# eg4duino_fin.net
KiCad netlist of a schematic drawn in EAGLE
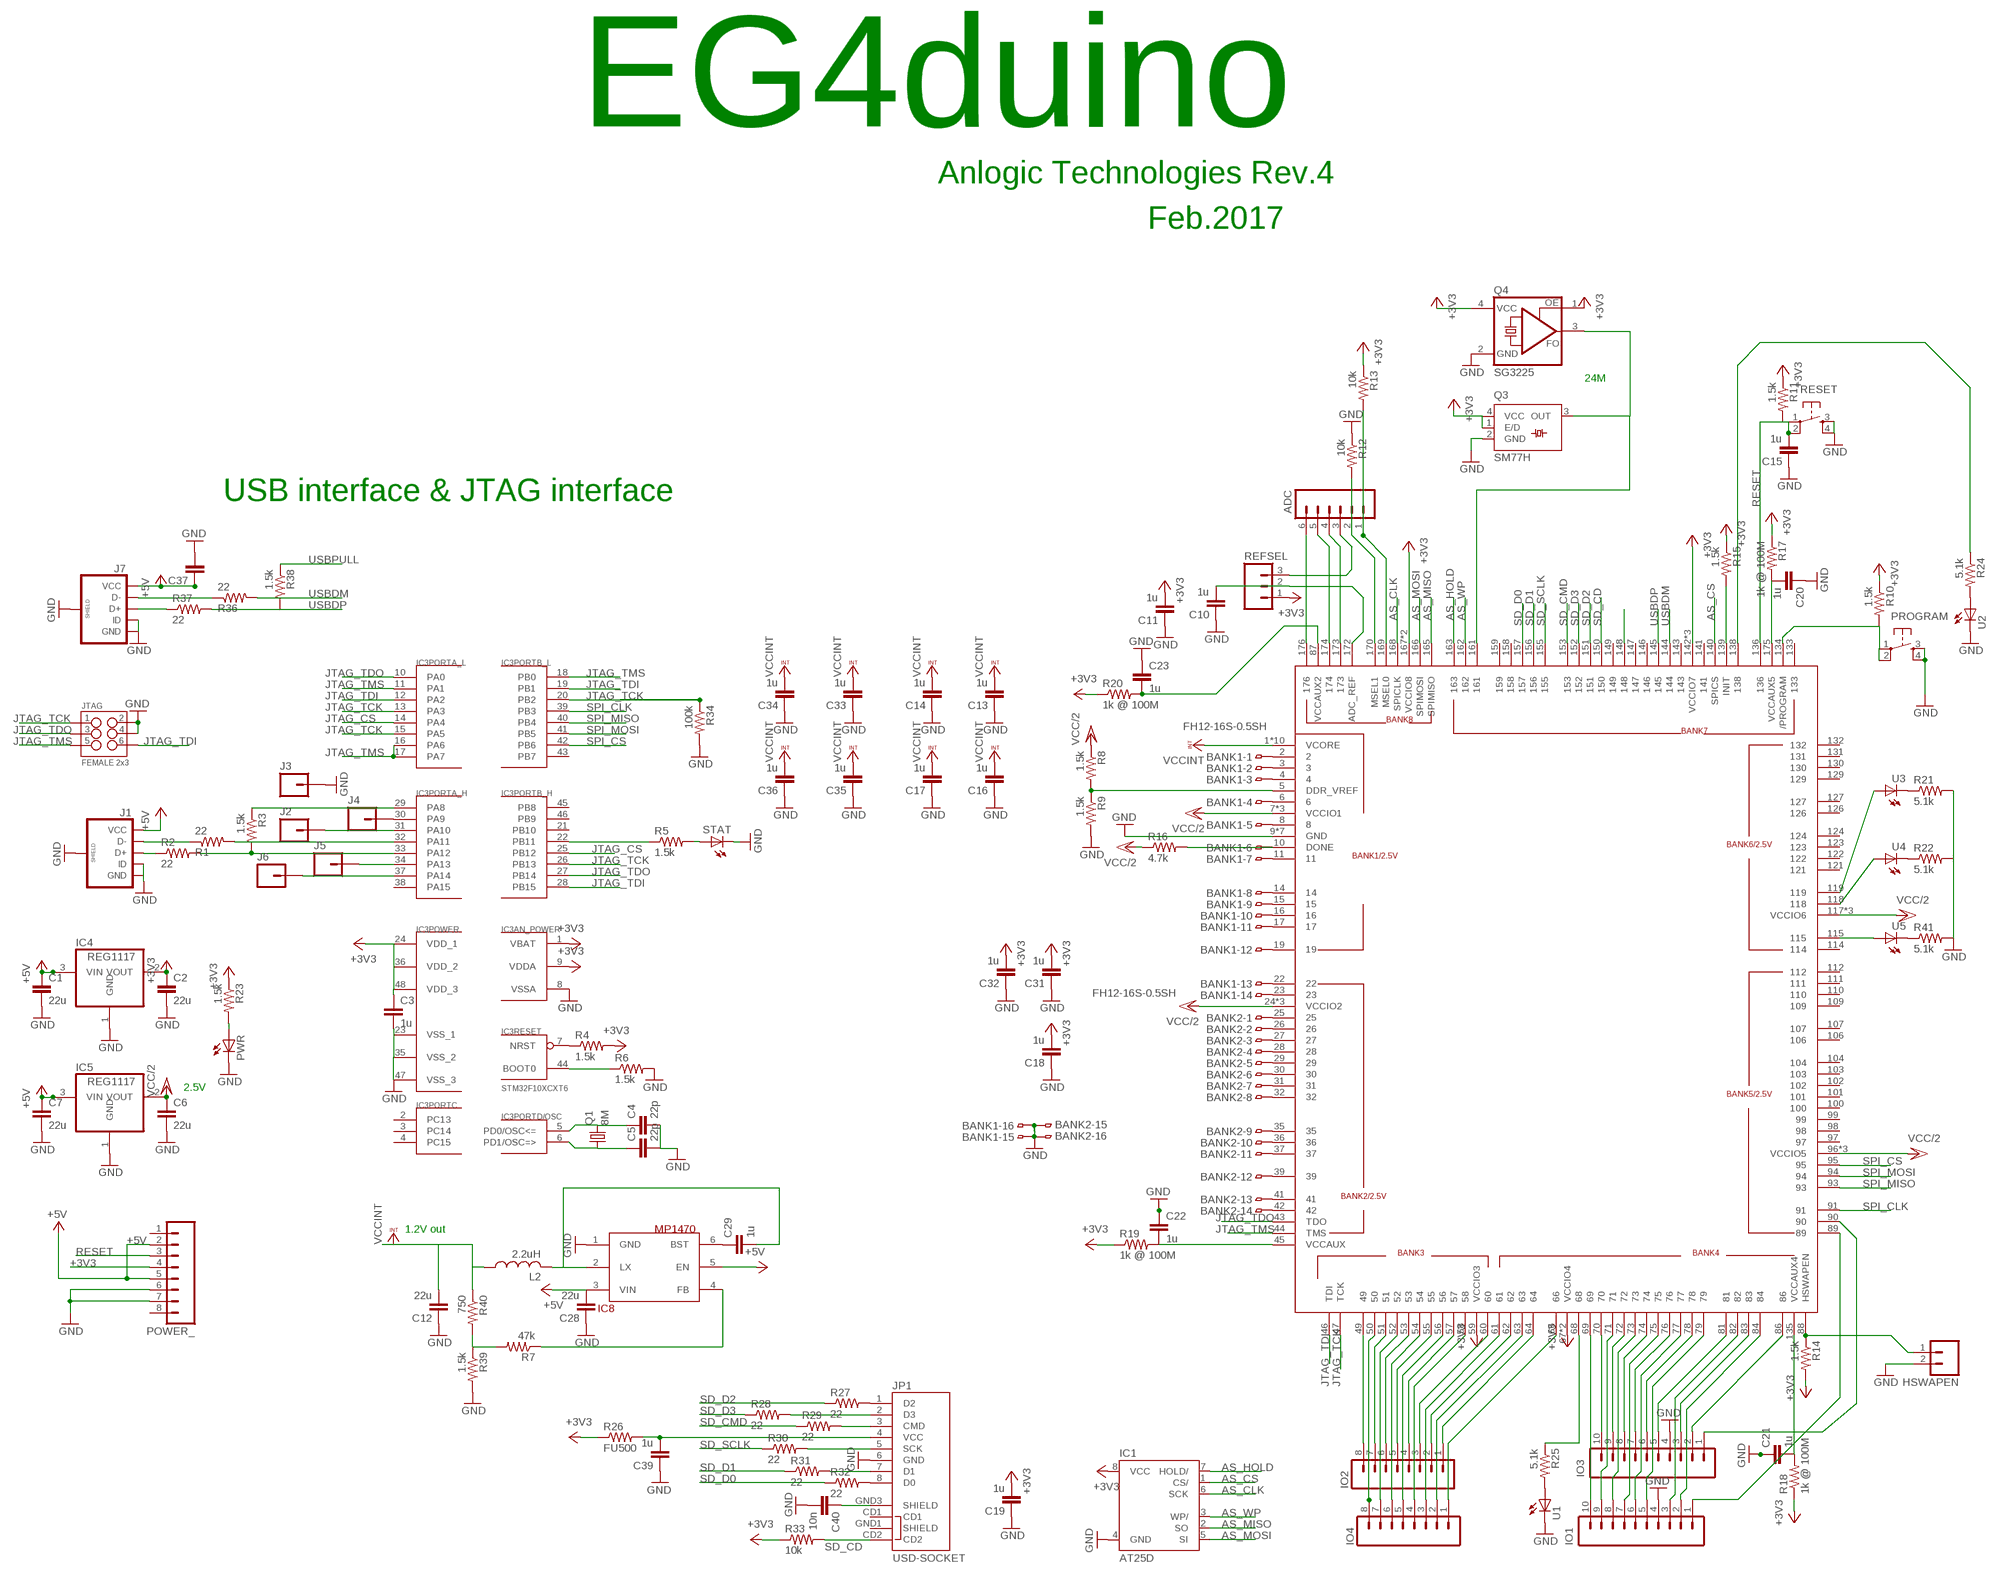
[diagram p0: schematic, sheet 1, part 1 of 2]
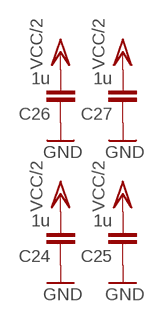
[diagram p1: schematic, sheet 1, part 2 of 2]

(export (version "E")
  (design (tool "Eeschema 10.0.6"))
  (components
    (comp (ref "ADC")
      (value "M06SILK_FEMALE_PTH")
      (footprint "eagle-import:1X06")
      (libsource (lib "eagle-import") (part "M06SILK_FEMALE_PTH"))
    )
    (comp (ref "BANK1")
      (value "FH12-16S-0.5SH")
      (footprint "eagle-import:FH12-16S-0.5SH")
      (fields (field (name "MPN") "FH12-16S-0.5SH(55)"))
      (libsource (lib "eagle-import") (part "FH12-16S-0.5SH"))
    )
    (comp (ref "BANK2")
      (value "FH12-16S-0.5SH")
      (footprint "eagle-import:FH12-16S-0.5SH")
      (fields (field (name "MPN") "FH12-16S-0.5SH(55)"))
      (libsource (lib "eagle-import") (part "FH12-16S-0.5SH"))
    )
    (comp (ref "C1")
      (value "22u")
      (footprint "eagle-import:C0805")
      (libsource (lib "eagle-import") (part "C-EUC0805"))
    )
    (comp (ref "C2")
      (value "22u")
      (footprint "eagle-import:C0805")
      (libsource (lib "eagle-import") (part "C-EUC0805"))
    )
    (comp (ref "C3")
      (value "1u")
      (footprint "eagle-import:C0805")
      (libsource (lib "eagle-import") (part "C-EUC0805"))
    )
    (comp (ref "C4")
      (value "22p")
      (footprint "eagle-import:C0805")
      (libsource (lib "eagle-import") (part "C-EUC0805"))
    )
    (comp (ref "C5")
      (value "22p")
      (footprint "eagle-import:C0805")
      (libsource (lib "eagle-import") (part "C-EUC0805"))
    )
    (comp (ref "C6")
      (value "22u")
      (footprint "eagle-import:C0805")
      (libsource (lib "eagle-import") (part "C-EUC0805"))
    )
    (comp (ref "C7")
      (value "22u")
      (footprint "eagle-import:C0805")
      (libsource (lib "eagle-import") (part "C-EUC0805"))
    )
    (comp (ref "C10")
      (value "1u")
      (footprint "eagle-import:C0805")
      (libsource (lib "eagle-import") (part "C-EUC0805"))
    )
    (comp (ref "C11")
      (value "1u")
      (footprint "eagle-import:C0805")
      (libsource (lib "eagle-import") (part "C-EUC0805"))
    )
    (comp (ref "C12")
      (value "22u")
      (footprint "eagle-import:C0805")
      (libsource (lib "eagle-import") (part "C-EUC0805"))
    )
    (comp (ref "C13")
      (value "1u")
      (footprint "eagle-import:C0805")
      (libsource (lib "eagle-import") (part "C-EUC0805"))
    )
    (comp (ref "C14")
      (value "1u")
      (footprint "eagle-import:C0805")
      (libsource (lib "eagle-import") (part "C-EUC0805"))
    )
    (comp (ref "C15")
      (value "1u")
      (footprint "eagle-import:C0805")
      (libsource (lib "eagle-import") (part "C-EUC0805"))
    )
    (comp (ref "C16")
      (value "1u")
      (footprint "eagle-import:C0805")
      (libsource (lib "eagle-import") (part "C-EUC0805"))
    )
    (comp (ref "C17")
      (value "1u")
      (footprint "eagle-import:C0805")
      (libsource (lib "eagle-import") (part "C-EUC0805"))
    )
    (comp (ref "C18")
      (value "1u")
      (footprint "eagle-import:C0805")
      (libsource (lib "eagle-import") (part "C-EUC0805"))
    )
    (comp (ref "C19")
      (value "1u")
      (footprint "eagle-import:C0805")
      (libsource (lib "eagle-import") (part "C-EUC0805"))
    )
    (comp (ref "C20")
      (value "1u")
      (footprint "eagle-import:C0805")
      (libsource (lib "eagle-import") (part "C-EUC0805"))
    )
    (comp (ref "C21")
      (value "1u")
      (footprint "eagle-import:C0805")
      (libsource (lib "eagle-import") (part "C-EUC0805"))
    )
    (comp (ref "C22")
      (value "1u")
      (footprint "eagle-import:C0805")
      (libsource (lib "eagle-import") (part "C-EUC0805"))
    )
    (comp (ref "C23")
      (value "1u")
      (footprint "eagle-import:C0805")
      (libsource (lib "eagle-import") (part "C-EUC0805"))
    )
    (comp (ref "C24")
      (value "1u")
      (footprint "eagle-import:C0805")
      (libsource (lib "eagle-import") (part "C-EUC0805"))
    )
    (comp (ref "C25")
      (value "1u")
      (footprint "eagle-import:C0805")
      (libsource (lib "eagle-import") (part "C-EUC0805"))
    )
    (comp (ref "C26")
      (value "1u")
      (footprint "eagle-import:C0805")
      (libsource (lib "eagle-import") (part "C-EUC0805"))
    )
    (comp (ref "C27")
      (value "1u")
      (footprint "eagle-import:C0805")
      (libsource (lib "eagle-import") (part "C-EUC0805"))
    )
    (comp (ref "C28")
      (value "22u")
      (footprint "eagle-import:C0805")
      (libsource (lib "eagle-import") (part "C-EUC0805"))
    )
    (comp (ref "C29")
      (value "1u")
      (footprint "eagle-import:C0805")
      (libsource (lib "eagle-import") (part "C-EUC0805"))
    )
    (comp (ref "C31")
      (value "1u")
      (footprint "eagle-import:C0805")
      (libsource (lib "eagle-import") (part "C-EUC0805"))
    )
    (comp (ref "C32")
      (value "1u")
      (footprint "eagle-import:C0805")
      (libsource (lib "eagle-import") (part "C-EUC0805"))
    )
    (comp (ref "C33")
      (value "1u")
      (footprint "eagle-import:C0805")
      (libsource (lib "eagle-import") (part "C-EUC0805"))
    )
    (comp (ref "C34")
      (value "1u")
      (footprint "eagle-import:C0805")
      (libsource (lib "eagle-import") (part "C-EUC0805"))
    )
    (comp (ref "C35")
      (value "1u")
      (footprint "eagle-import:C0805")
      (libsource (lib "eagle-import") (part "C-EUC0805"))
    )
    (comp (ref "C36")
      (value "1u")
      (footprint "eagle-import:C0805")
      (libsource (lib "eagle-import") (part "C-EUC0805"))
    )
    (comp (ref "C37")
      (value "C-EUC0805")
      (footprint "eagle-import:C0805")
      (libsource (lib "eagle-import") (part "C-EUC0805"))
    )
    (comp (ref "C39")
      (value "1u")
      (footprint "eagle-import:C0805")
      (libsource (lib "eagle-import") (part "C-EUC0805"))
    )
    (comp (ref "C40")
      (value "10n")
      (footprint "eagle-import:C0805")
      (libsource (lib "eagle-import") (part "C-EUC0805"))
    )
    (comp (ref "HSWAPEN")
      (value "M02PTH")
      (footprint "eagle-import:1X02")
      (libsource (lib "eagle-import") (part "M02PTH"))
    )
    (comp (ref "IC1")
      (value "AT25D")
      (footprint "eagle-import:SOIC8")
      (libsource (lib "eagle-import") (part "AT25D"))
    )
    (comp (ref "IC2")
      (value "EG4D20EG176")
      (footprint "eagle-import:ELQFP176L")
      (libsource (lib "eagle-import") (part "EG4D20EG176"))
    )
    (comp (ref "IC3")
      (value "STM32F10XCXT6")
      (footprint "eagle-import:TQFP48")
      (libsource (lib "eagle-import") (part "STM32F10XCXT6"))
    )
    (comp (ref "IC4")
      (value "REG1117")
      (footprint "eagle-import:SOT223")
      (libsource (lib "eagle-import") (part "REG1117"))
    )
    (comp (ref "IC5")
      (value "REG1117")
      (footprint "eagle-import:SOT223")
      (libsource (lib "eagle-import") (part "REG1117"))
    )
    (comp (ref "IC8")
      (value "MP1470")
      (footprint "eagle-import:SOT23-6L")
      (libsource (lib "eagle-import") (part "MP1470"))
    )
    (comp (ref "IO1")
      (value "M10SILK_FEMALE_PTH")
      (footprint "eagle-import:1X10")
      (libsource (lib "eagle-import") (part "M10SILK_FEMALE_PTH"))
    )
    (comp (ref "IO2")
      (value "M08SILK_FEMALE_PTH")
      (footprint "eagle-import:1X08")
      (libsource (lib "eagle-import") (part "M08SILK_FEMALE_PTH"))
    )
    (comp (ref "IO3")
      (value "M10SILK_FEMALE_PTH")
      (footprint "eagle-import:1X10")
      (libsource (lib "eagle-import") (part "M10SILK_FEMALE_PTH"))
    )
    (comp (ref "IO4")
      (value "M08SILK_FEMALE_PTH")
      (footprint "eagle-import:1X08")
      (libsource (lib "eagle-import") (part "M08SILK_FEMALE_PTH"))
    )
    (comp (ref "J1")
      (value "USB_MICROB_PLUGCONN-11752")
      (footprint "eagle-import:USB-B-MICRO-SMD_V03")
      (libsource (lib "eagle-import") (part "USB_MICROB_PLUGCONN-11752"))
    )
    (comp (ref "J2")
      (value "M01")
      (footprint "eagle-import:0805SMD")
      (libsource (lib "eagle-import") (part "M01"))
    )
    (comp (ref "J3")
      (value "M01")
      (footprint "eagle-import:0805SMD")
      (libsource (lib "eagle-import") (part "M01"))
    )
    (comp (ref "J4")
      (value "M01")
      (footprint "eagle-import:0805SMD")
      (libsource (lib "eagle-import") (part "M01"))
    )
    (comp (ref "J5")
      (value "M01")
      (footprint "eagle-import:0805SMD")
      (libsource (lib "eagle-import") (part "M01"))
    )
    (comp (ref "J6")
      (value "M01")
      (footprint "eagle-import:0805SMD")
      (libsource (lib "eagle-import") (part "M01"))
    )
    (comp (ref "J7")
      (value "USB_MICROB_PLUGCONN-11752")
      (footprint "eagle-import:USB-B-MICRO-SMD_V03")
      (libsource (lib "eagle-import") (part "USB_MICROB_PLUGCONN-11752"))
    )
    (comp (ref "JP1")
      (value "USD-SOCKET")
      (footprint "eagle-import:MICROSD_1_1")
      (libsource (lib "eagle-import") (part "USD-SOCKET"))
    )
    (comp (ref "JTAG")
      (value "FEMALE 2x3")
      (footprint "eagle-import:2X3")
      (libsource (lib "eagle-import") (part "M03X2FEMALE"))
    )
    (comp (ref "L2")
      (value "2.2uH")
      (footprint "eagle-import:L4532P")
      (libsource (lib "eagle-import") (part "L-USL4532P"))
    )
    (comp (ref "POWER_")
      (value "M08SILK_FEMALE_PTH")
      (footprint "eagle-import:1X08")
      (libsource (lib "eagle-import") (part "M08SILK_FEMALE_PTH"))
    )
    (comp (ref "PROGRAM")
      (value "10-XXSMD")
      (footprint "eagle-import:B3F-10SMD")
      (libsource (lib "eagle-import") (part "10-XXSMD"))
    )
    (comp (ref "PWR")
      (value "LEDCHIP-LED0805")
      (footprint "eagle-import:CHIP-LED0805")
      (libsource (lib "eagle-import") (part "LEDCHIP-LED0805"))
    )
    (comp (ref "Q1")
      (value "8M")
      (footprint "eagle-import:HC49_S")
      (libsource (lib "eagle-import") (part "CRYSTALHC49S"))
    )
    (comp (ref "Q3")
      (value "SM77H")
      (footprint "eagle-import:SM77H")
      (libsource (lib "eagle-import") (part "SM77H"))
    )
    (comp (ref "Q4")
      (value "SG3225")
      (footprint "eagle-import:3225")
      (libsource (lib "eagle-import") (part "SG3225"))
    )
    (comp (ref "R1")
      (value "22")
      (footprint "eagle-import:M0805")
      (libsource (lib "eagle-import") (part "R-US_M0805"))
    )
    (comp (ref "R2")
      (value "22")
      (footprint "eagle-import:M0805")
      (libsource (lib "eagle-import") (part "R-US_M0805"))
    )
    (comp (ref "R3")
      (value "1.5k")
      (footprint "eagle-import:M0805")
      (libsource (lib "eagle-import") (part "R-US_M0805"))
    )
    (comp (ref "R4")
      (value "1.5k")
      (footprint "eagle-import:M0805")
      (libsource (lib "eagle-import") (part "R-US_M0805"))
    )
    (comp (ref "R5")
      (value "1.5k")
      (footprint "eagle-import:M0805")
      (libsource (lib "eagle-import") (part "R-US_M0805"))
    )
    (comp (ref "R6")
      (value "1.5k")
      (footprint "eagle-import:M0805")
      (libsource (lib "eagle-import") (part "R-US_M0805"))
    )
    (comp (ref "R7")
      (value "47k")
      (footprint "eagle-import:R0805")
      (libsource (lib "eagle-import") (part "R-US_R0805"))
    )
    (comp (ref "R8")
      (value "1.5k")
      (footprint "eagle-import:R0805")
      (libsource (lib "eagle-import") (part "R-US_R0805"))
    )
    (comp (ref "R9")
      (value "1.5k")
      (footprint "eagle-import:R0805")
      (libsource (lib "eagle-import") (part "R-US_R0805"))
    )
    (comp (ref "R10")
      (value "1.5k")
      (footprint "eagle-import:R0603")
      (libsource (lib "eagle-import") (part "R-US_R0603"))
    )
    (comp (ref "R11")
      (value "1.5k")
      (footprint "eagle-import:R0805")
      (libsource (lib "eagle-import") (part "R-US_R0805"))
    )
    (comp (ref "R12")
      (value "10k")
      (footprint "eagle-import:R0805")
      (libsource (lib "eagle-import") (part "R-US_R0805"))
    )
    (comp (ref "R13")
      (value "10k")
      (footprint "eagle-import:R0805")
      (libsource (lib "eagle-import") (part "R-US_R0805"))
    )
    (comp (ref "R14")
      (value "1.5k")
      (footprint "eagle-import:R0805")
      (libsource (lib "eagle-import") (part "R-US_R0805"))
    )
    (comp (ref "R15")
      (value "1.5k")
      (footprint "eagle-import:R0805")
      (libsource (lib "eagle-import") (part "R-US_R0805"))
    )
    (comp (ref "R16")
      (value "4.7k")
      (footprint "eagle-import:R0603")
      (libsource (lib "eagle-import") (part "R-US_R0603"))
    )
    (comp (ref "R17")
      (value "1k @ 100M")
      (footprint "eagle-import:R0805")
      (libsource (lib "eagle-import") (part "R-US_R0805"))
    )
    (comp (ref "R18")
      (value "1k @ 100M")
      (footprint "eagle-import:R0805")
      (libsource (lib "eagle-import") (part "R-US_R0805"))
    )
    (comp (ref "R19")
      (value "1k @ 100M")
      (footprint "eagle-import:R0805")
      (libsource (lib "eagle-import") (part "R-US_R0805"))
    )
    (comp (ref "R20")
      (value "1k @ 100M")
      (footprint "eagle-import:R0805")
      (libsource (lib "eagle-import") (part "R-US_R0805"))
    )
    (comp (ref "R21")
      (value "5.1k")
      (footprint "eagle-import:M0805")
      (libsource (lib "eagle-import") (part "R-US_M0805"))
    )
    (comp (ref "R22")
      (value "5.1k")
      (footprint "eagle-import:M0805")
      (libsource (lib "eagle-import") (part "R-US_M0805"))
    )
    (comp (ref "R23")
      (value "1.5k")
      (footprint "eagle-import:M0805")
      (libsource (lib "eagle-import") (part "R-US_M0805"))
    )
    (comp (ref "R24")
      (value "5.1k")
      (footprint "eagle-import:M0805")
      (libsource (lib "eagle-import") (part "R-US_M0805"))
    )
    (comp (ref "R25")
      (value "5.1k")
      (footprint "eagle-import:M0805")
      (libsource (lib "eagle-import") (part "R-US_M0805"))
    )
    (comp (ref "R26")
      (value "FU500")
      (footprint "eagle-import:R0805")
      (libsource (lib "eagle-import") (part "R-US_R0805"))
    )
    (comp (ref "R27")
      (value "22")
      (footprint "eagle-import:R0201")
      (libsource (lib "eagle-import") (part "R-US_R0201"))
    )
    (comp (ref "R28")
      (value "22")
      (footprint "eagle-import:R0201")
      (libsource (lib "eagle-import") (part "R-US_R0201"))
    )
    (comp (ref "R29")
      (value "22")
      (footprint "eagle-import:R0201")
      (libsource (lib "eagle-import") (part "R-US_R0201"))
    )
    (comp (ref "R30")
      (value "22")
      (footprint "eagle-import:R0201")
      (libsource (lib "eagle-import") (part "R-US_R0201"))
    )
    (comp (ref "R31")
      (value "22")
      (footprint "eagle-import:R0201")
      (libsource (lib "eagle-import") (part "R-US_R0201"))
    )
    (comp (ref "R32")
      (value "22")
      (footprint "eagle-import:R0201")
      (libsource (lib "eagle-import") (part "R-US_R0201"))
    )
    (comp (ref "R33")
      (value "10k")
      (footprint "eagle-import:R0805")
      (libsource (lib "eagle-import") (part "R-US_R0805"))
    )
    (comp (ref "R34")
      (value "100k")
      (footprint "eagle-import:R0603")
      (libsource (lib "eagle-import") (part "R-US_R0603"))
    )
    (comp (ref "R36")
      (value "22")
      (footprint "eagle-import:R0603W")
      (libsource (lib "eagle-import") (part "R-US_R0603W"))
    )
    (comp (ref "R37")
      (value "22")
      (footprint "eagle-import:R0603W")
      (libsource (lib "eagle-import") (part "R-US_R0603W"))
    )
    (comp (ref "R38")
      (value "1.5k")
      (footprint "eagle-import:R0603")
      (libsource (lib "eagle-import") (part "R-US_R0603"))
    )
    (comp (ref "R39")
      (value "1.5k")
      (footprint "eagle-import:R0805")
      (libsource (lib "eagle-import") (part "R-US_R0805"))
    )
    (comp (ref "R40")
      (value "750")
      (footprint "eagle-import:R0805")
      (libsource (lib "eagle-import") (part "R-US_R0805"))
    )
    (comp (ref "R41")
      (value "5.1k")
      (footprint "eagle-import:M0805")
      (libsource (lib "eagle-import") (part "R-US_M0805"))
    )
    (comp (ref "REFSEL")
      (value "M03PTH")
      (footprint "eagle-import:1X03")
      (libsource (lib "eagle-import") (part "M03PTH"))
    )
    (comp (ref "RESET")
      (value "10-XXSMD")
      (footprint "eagle-import:B3F-10SMD")
      (libsource (lib "eagle-import") (part "10-XXSMD"))
    )
    (comp (ref "STAT")
      (value "LEDCHIP-LED0805")
      (footprint "eagle-import:CHIP-LED0805")
      (libsource (lib "eagle-import") (part "LEDCHIP-LED0805"))
    )
    (comp (ref "U1")
      (value "LEDCHIP-LED0805")
      (footprint "eagle-import:CHIP-LED0805")
      (libsource (lib "eagle-import") (part "LEDCHIP-LED0805"))
    )
    (comp (ref "U2")
      (value "LEDCHIP-LED0805")
      (footprint "eagle-import:CHIP-LED0805")
      (libsource (lib "eagle-import") (part "LEDCHIP-LED0805"))
    )
    (comp (ref "U3")
      (value "LEDCHIP-LED0805")
      (footprint "eagle-import:CHIP-LED0805")
      (libsource (lib "eagle-import") (part "LEDCHIP-LED0805"))
    )
    (comp (ref "U4")
      (value "LEDCHIP-LED0805")
      (footprint "eagle-import:CHIP-LED0805")
      (libsource (lib "eagle-import") (part "LEDCHIP-LED0805"))
    )
    (comp (ref "U5")
      (value "LEDCHIP-LED0805")
      (footprint "eagle-import:CHIP-LED0805")
      (libsource (lib "eagle-import") (part "LEDCHIP-LED0805"))
    )
  )
  (nets
    (net (code "1") (name "+3V3") (class "Default")
      (node (ref "C11") (pin "2") (pinfunction "2_2") (pintype "passive"))
      (node (ref "C18") (pin "2") (pinfunction "2_2") (pintype "passive"))
      (node (ref "C19") (pin "2") (pinfunction "2_2") (pintype "passive"))
      (node (ref "C2") (pin "1") (pinfunction "1_1") (pintype "passive"))
      (node (ref "C3") (pin "1") (pinfunction "1_1") (pintype "passive"))
      (node (ref "C31") (pin "2") (pinfunction "2_2") (pintype "passive"))
      (node (ref "C32") (pin "2") (pinfunction "2_2") (pintype "passive"))
      (node (ref "IC1") (pin "8") (pinfunction "VCC_8") (pintype "power_in"))
      (node (ref "IC2") (pin "142") (pinfunction "VCCIO7_142") (pintype "bidirectional"))
      (node (ref "IC2") (pin "154") (pinfunction "VCCIO7_154") (pintype "bidirectional"))
      (node (ref "IC2") (pin "160") (pinfunction "VCCIO7_160") (pintype "bidirectional"))
      (node (ref "IC2") (pin "167") (pinfunction "VCCIO8_167") (pintype "bidirectional"))
      (node (ref "IC2") (pin "171") (pinfunction "VCCIO8_171") (pintype "bidirectional"))
      (node (ref "IC2") (pin "59") (pinfunction "VCCIO3_59") (pintype "bidirectional"))
      (node (ref "IC2") (pin "67") (pinfunction "VCCIO4_67") (pintype "bidirectional"))
      (node (ref "IC2") (pin "80") (pinfunction "VCCIO4_80") (pintype "bidirectional"))
      (node (ref "IC3") (pin "1") (pinfunction "VBAT_1") (pintype "power_in"))
      (node (ref "IC3") (pin "24") (pinfunction "VDD_1_24") (pintype "power_in"))
      (node (ref "IC3") (pin "36") (pinfunction "VDD_2_36") (pintype "power_in"))
      (node (ref "IC3") (pin "48") (pinfunction "VDD_3_48") (pintype "power_in"))
      (node (ref "IC3") (pin "9") (pinfunction "VDDA_9") (pintype "power_in"))
      (node (ref "IC4") (pin "2") (pinfunction "VOUT_2") (pintype "output"))
      (node (ref "POWER_") (pin "4") (pinfunction "4_4") (pintype "passive"))
      (node (ref "Q3") (pin "1") (pinfunction "E/D_1") (pintype "input"))
      (node (ref "Q3") (pin "4") (pinfunction "VCC_4") (pintype "power_in"))
      (node (ref "Q4") (pin "1") (pinfunction "OE_1") (pintype "input"))
      (node (ref "Q4") (pin "4") (pinfunction "VCC_4") (pintype "power_in"))
      (node (ref "R10") (pin "1") (pinfunction "1_1") (pintype "passive"))
      (node (ref "R11") (pin "1") (pinfunction "1_1") (pintype "passive"))
      (node (ref "R13") (pin "1") (pinfunction "1_1") (pintype "passive"))
      (node (ref "R14") (pin "2") (pinfunction "2_2") (pintype "passive"))
      (node (ref "R15") (pin "1") (pinfunction "1_1") (pintype "passive"))
      (node (ref "R17") (pin "1") (pinfunction "1_1") (pintype "passive"))
      (node (ref "R18") (pin "1") (pinfunction "1_1") (pintype "passive"))
      (node (ref "R19") (pin "1") (pinfunction "1_1") (pintype "passive"))
      (node (ref "R20") (pin "1") (pinfunction "1_1") (pintype "passive"))
      (node (ref "R23") (pin "1") (pinfunction "1_1") (pintype "passive"))
      (node (ref "R26") (pin "1") (pinfunction "1_1") (pintype "passive"))
      (node (ref "R33") (pin "1") (pinfunction "1_1") (pintype "passive"))
      (node (ref "R4") (pin "2") (pinfunction "2_2") (pintype "passive"))
      (node (ref "REFSEL") (pin "1") (pinfunction "1_1") (pintype "passive"))
    )
    (net (code "2") (name "+5V") (class "Default")
      (node (ref "C1") (pin "1") (pinfunction "1_1") (pintype "passive"))
      (node (ref "C28") (pin "2") (pinfunction "2_2") (pintype "passive"))
      (node (ref "C37") (pin "1") (pinfunction "1_1") (pintype "passive"))
      (node (ref "C7") (pin "1") (pinfunction "1_1") (pintype "passive"))
      (node (ref "IC4") (pin "3") (pinfunction "VIN_3") (pintype "input"))
      (node (ref "IC5") (pin "3") (pinfunction "VIN_3") (pintype "input"))
      (node (ref "IC8") (pin "3") (pinfunction "VIN_3") (pintype "power_in"))
      (node (ref "IC8") (pin "5") (pinfunction "EN_5") (pintype "bidirectional"))
      (node (ref "J1") (pin "VBUS") (pinfunction "VCC_VBUS") (pintype "bidirectional"))
      (node (ref "J7") (pin "VBUS") (pinfunction "VCC_VBUS") (pintype "bidirectional"))
      (node (ref "POWER_") (pin "2") (pinfunction "2_2") (pintype "passive"))
      (node (ref "POWER_") (pin "5") (pinfunction "5_5") (pintype "passive"))
    )
    (net (code "3") (name "/AS_CLK") (class "Default")
      (node (ref "IC1") (pin "6") (pinfunction "SCK_6") (pintype "bidirectional"))
      (node (ref "IC2") (pin "168") (pinfunction "SPICLK_168") (pintype "bidirectional"))
    )
    (net (code "4") (name "/AS_CS") (class "Default")
      (node (ref "IC1") (pin "1") (pinfunction "CS/_1") (pintype "input"))
      (node (ref "IC2") (pin "140") (pinfunction "SPICS_140") (pintype "bidirectional"))
    )
    (net (code "5") (name "/AS_HOLD") (class "Default")
      (node (ref "IC1") (pin "7") (pinfunction "HOLD/_7") (pintype "input"))
      (node (ref "IC2") (pin "163") (pinfunction "163_163") (pintype "bidirectional"))
    )
    (net (code "6") (name "/AS_MISO") (class "Default")
      (node (ref "IC1") (pin "2") (pinfunction "SO_2") (pintype "input"))
      (node (ref "IC2") (pin "165") (pinfunction "SPIMISO_165") (pintype "bidirectional"))
    )
    (net (code "7") (name "/AS_MOSI") (class "Default")
      (node (ref "IC1") (pin "5") (pinfunction "SI_5") (pintype "bidirectional"))
      (node (ref "IC2") (pin "166") (pinfunction "SPIMOSI_166") (pintype "bidirectional"))
    )
    (net (code "8") (name "/AS_WP") (class "Default")
      (node (ref "IC1") (pin "3") (pinfunction "WP/_3") (pintype "input"))
      (node (ref "IC2") (pin "162") (pinfunction "162_162") (pintype "bidirectional"))
    )
    (net (code "9") (name "/JTAG_CS") (class "Default")
      (node (ref "IC3") (pin "14") (pinfunction "PA4_14") (pintype "bidirectional"))
      (node (ref "IC3") (pin "25") (pinfunction "PB12_25") (pintype "bidirectional"))
    )
    (net (code "10") (name "/JTAG_TCK") (class "Default")
      (node (ref "IC2") (pin "47") (pinfunction "TCK_47") (pintype "bidirectional"))
      (node (ref "IC3") (pin "13") (pinfunction "PA3_13") (pintype "bidirectional"))
      (node (ref "IC3") (pin "15") (pinfunction "PA5_15") (pintype "bidirectional"))
      (node (ref "IC3") (pin "20") (pinfunction "PB2_20") (pintype "bidirectional"))
      (node (ref "IC3") (pin "26") (pinfunction "PB13_26") (pintype "bidirectional"))
      (node (ref "JTAG") (pin "1") (pinfunction "1_1") (pintype "bidirectional"))
      (node (ref "R34") (pin "1") (pinfunction "1_1") (pintype "passive"))
    )
    (net (code "11") (name "/JTAG_TDI") (class "Default")
      (node (ref "IC2") (pin "46") (pinfunction "TDI_46") (pintype "bidirectional"))
      (node (ref "IC3") (pin "12") (pinfunction "PA2_12") (pintype "bidirectional"))
      (node (ref "IC3") (pin "19") (pinfunction "PB1_19") (pintype "bidirectional"))
      (node (ref "IC3") (pin "28") (pinfunction "PB15_28") (pintype "bidirectional"))
      (node (ref "JTAG") (pin "6") (pinfunction "6_6") (pintype "bidirectional"))
    )
    (net (code "12") (name "/JTAG_TDO") (class "Default")
      (node (ref "IC2") (pin "43") (pinfunction "TDO_43") (pintype "bidirectional"))
      (node (ref "IC3") (pin "10") (pinfunction "PA0_10") (pintype "bidirectional"))
      (node (ref "IC3") (pin "27") (pinfunction "PB14_27") (pintype "bidirectional"))
      (node (ref "JTAG") (pin "3") (pinfunction "3_3") (pintype "bidirectional"))
    )
    (net (code "13") (name "/JTAG_TMS") (class "Default")
      (node (ref "IC2") (pin "44") (pinfunction "TMS_44") (pintype "bidirectional"))
      (node (ref "IC3") (pin "11") (pinfunction "PA1_11") (pintype "bidirectional"))
      (node (ref "IC3") (pin "16") (pinfunction "PA6_16") (pintype "bidirectional"))
      (node (ref "IC3") (pin "17") (pinfunction "PA7_17") (pintype "bidirectional"))
      (node (ref "IC3") (pin "18") (pinfunction "PB0_18") (pintype "bidirectional"))
      (node (ref "JTAG") (pin "5") (pinfunction "5_5") (pintype "bidirectional"))
    )
    (net (code "14") (name "/RESET") (class "Default")
      (node (ref "C15") (pin "2") (pinfunction "2_2") (pintype "passive"))
      (node (ref "IC2") (pin "136") (pinfunction "136_136") (pintype "bidirectional"))
      (node (ref "POWER_") (pin "3") (pinfunction "3_3") (pintype "passive"))
      (node (ref "R11") (pin "2") (pinfunction "2_2") (pintype "passive"))
      (node (ref "RESET") (pin "1") (pinfunction "P_1") (pintype "passive"))
      (node (ref "RESET") (pin "2") (pinfunction "P1_2") (pintype "passive"))
    )
    (net (code "15") (name "/SD_CD") (class "Default")
      (node (ref "IC2") (pin "150") (pinfunction "150_150") (pintype "bidirectional"))
      (node (ref "JP1") (pin "CD2") (pinfunction "CD2_CD2") (pintype "bidirectional"))
      (node (ref "R33") (pin "2") (pinfunction "2_2") (pintype "passive"))
    )
    (net (code "16") (name "/SD_CMD") (class "Default")
      (node (ref "IC2") (pin "153") (pinfunction "153_153") (pintype "bidirectional"))
      (node (ref "R29") (pin "1") (pinfunction "1_1") (pintype "passive"))
    )
    (net (code "17") (name "/SD_D0") (class "Default")
      (node (ref "IC2") (pin "157") (pinfunction "157_157") (pintype "bidirectional"))
      (node (ref "R32") (pin "1") (pinfunction "1_1") (pintype "passive"))
    )
    (net (code "18") (name "/SD_D1") (class "Default")
      (node (ref "IC2") (pin "156") (pinfunction "156_156") (pintype "bidirectional"))
      (node (ref "R31") (pin "1") (pinfunction "1_1") (pintype "passive"))
    )
    (net (code "19") (name "/SD_D2") (class "Default")
      (node (ref "IC2") (pin "151") (pinfunction "151_151") (pintype "bidirectional"))
      (node (ref "R27") (pin "1") (pinfunction "1_1") (pintype "passive"))
    )
    (net (code "20") (name "/SD_D3") (class "Default")
      (node (ref "IC2") (pin "152") (pinfunction "152_152") (pintype "bidirectional"))
      (node (ref "R28") (pin "1") (pinfunction "1_1") (pintype "passive"))
    )
    (net (code "21") (name "/SD_SCLK") (class "Default")
      (node (ref "IC2") (pin "155") (pinfunction "155_155") (pintype "bidirectional"))
      (node (ref "R30") (pin "1") (pinfunction "1_1") (pintype "passive"))
    )
    (net (code "22") (name "/SPI_CLK") (class "Default")
      (node (ref "IC2") (pin "91") (pinfunction "91_91") (pintype "bidirectional"))
      (node (ref "IC3") (pin "39") (pinfunction "PB3_39") (pintype "bidirectional"))
    )
    (net (code "23") (name "/SPI_CS") (class "Default")
      (node (ref "IC2") (pin "95") (pinfunction "95_95") (pintype "bidirectional"))
      (node (ref "IC3") (pin "42") (pinfunction "PB6_42") (pintype "bidirectional"))
    )
    (net (code "24") (name "/SPI_MISO") (class "Default")
      (node (ref "IC2") (pin "93") (pinfunction "93_93") (pintype "bidirectional"))
      (node (ref "IC3") (pin "40") (pinfunction "PB4_40") (pintype "bidirectional"))
    )
    (net (code "25") (name "/SPI_MOSI") (class "Default")
      (node (ref "IC2") (pin "94") (pinfunction "94_94") (pintype "bidirectional"))
      (node (ref "IC3") (pin "41") (pinfunction "PB5_41") (pintype "bidirectional"))
    )
    (net (code "26") (name "/USBDM") (class "Default")
      (node (ref "IC2") (pin "144") (pinfunction "144_144") (pintype "bidirectional"))
      (node (ref "R36") (pin "2") (pinfunction "2_2") (pintype "passive"))
    )
    (net (code "27") (name "/USBDP") (class "Default")
      (node (ref "IC2") (pin "145") (pinfunction "145_145") (pintype "bidirectional"))
      (node (ref "R37") (pin "2") (pinfunction "2_2") (pintype "passive"))
      (node (ref "R38") (pin "2") (pinfunction "2_2") (pintype "passive"))
    )
    (net (code "28") (name "/USBPULL") (class "Default")
      (node (ref "IC2") (pin "148") (pinfunction "148_148") (pintype "bidirectional"))
      (node (ref "R38") (pin "1") (pinfunction "1_1") (pintype "passive"))
    )
    (net (code "29") (name "GND") (class "Default")
      (node (ref "BANK1") (pin "15") (pinfunction "1_15") (pintype "passive"))
      (node (ref "BANK1") (pin "16") (pinfunction "1_16") (pintype "passive"))
      (node (ref "BANK2") (pin "15") (pinfunction "1_15") (pintype "passive"))
      (node (ref "BANK2") (pin "16") (pinfunction "1_16") (pintype "passive"))
      (node (ref "C1") (pin "2") (pinfunction "2_2") (pintype "passive"))
      (node (ref "C10") (pin "1") (pinfunction "1_1") (pintype "passive"))
      (node (ref "C11") (pin "1") (pinfunction "1_1") (pintype "passive"))
      (node (ref "C12") (pin "1") (pinfunction "1_1") (pintype "passive"))
      (node (ref "C13") (pin "1") (pinfunction "1_1") (pintype "passive"))
      (node (ref "C14") (pin "1") (pinfunction "1_1") (pintype "passive"))
      (node (ref "C15") (pin "1") (pinfunction "1_1") (pintype "passive"))
      (node (ref "C16") (pin "1") (pinfunction "1_1") (pintype "passive"))
      (node (ref "C17") (pin "1") (pinfunction "1_1") (pintype "passive"))
      (node (ref "C18") (pin "1") (pinfunction "1_1") (pintype "passive"))
      (node (ref "C19") (pin "1") (pinfunction "1_1") (pintype "passive"))
      (node (ref "C2") (pin "2") (pinfunction "2_2") (pintype "passive"))
      (node (ref "C20") (pin "1") (pinfunction "1_1") (pintype "passive"))
      (node (ref "C21") (pin "1") (pinfunction "1_1") (pintype "passive"))
      (node (ref "C22") (pin "1") (pinfunction "1_1") (pintype "passive"))
      (node (ref "C23") (pin "1") (pinfunction "1_1") (pintype "passive"))
      (node (ref "C24") (pin "1") (pinfunction "1_1") (pintype "passive"))
      (node (ref "C25") (pin "1") (pinfunction "1_1") (pintype "passive"))
      (node (ref "C26") (pin "1") (pinfunction "1_1") (pintype "passive"))
      (node (ref "C27") (pin "1") (pinfunction "1_1") (pintype "passive"))
      (node (ref "C28") (pin "1") (pinfunction "1_1") (pintype "passive"))
      (node (ref "C3") (pin "2") (pinfunction "2_2") (pintype "passive"))
      (node (ref "C31") (pin "1") (pinfunction "1_1") (pintype "passive"))
      (node (ref "C32") (pin "1") (pinfunction "1_1") (pintype "passive"))
      (node (ref "C33") (pin "1") (pinfunction "1_1") (pintype "passive"))
      (node (ref "C34") (pin "1") (pinfunction "1_1") (pintype "passive"))
      (node (ref "C35") (pin "1") (pinfunction "1_1") (pintype "passive"))
      (node (ref "C36") (pin "1") (pinfunction "1_1") (pintype "passive"))
      (node (ref "C37") (pin "2") (pinfunction "2_2") (pintype "passive"))
      (node (ref "C39") (pin "1") (pinfunction "1_1") (pintype "passive"))
      (node (ref "C4") (pin "2") (pinfunction "2_2") (pintype "passive"))
      (node (ref "C40") (pin "2") (pinfunction "2_2") (pintype "passive"))
      (node (ref "C5") (pin "2") (pinfunction "2_2") (pintype "passive"))
      (node (ref "C6") (pin "2") (pinfunction "2_2") (pintype "passive"))
      (node (ref "C7") (pin "2") (pinfunction "2_2") (pintype "passive"))
      (node (ref "HSWAPEN") (pin "2") (pinfunction "2_2") (pintype "passive"))
      (node (ref "IC1") (pin "4") (pinfunction "GND_4") (pintype "power_in"))
      (node (ref "IC2") (pin "116") (pinfunction "GND_116") (pintype "bidirectional"))
      (node (ref "IC2") (pin "13") (pinfunction "GND_13") (pintype "bidirectional"))
      (node (ref "IC2") (pin "21") (pinfunction "GND_21") (pintype "bidirectional"))
      (node (ref "IC2") (pin "33") (pinfunction "GND_33") (pintype "bidirectional"))
      (node (ref "IC2") (pin "38") (pinfunction "GND_38") (pintype "bidirectional"))
      (node (ref "IC2") (pin "9") (pinfunction "GND_9") (pintype "bidirectional"))
      (node (ref "IC2") (pin "EGND") (pinfunction "GND_EGND") (pintype "bidirectional"))
      (node (ref "IC3") (pin "23") (pinfunction "VSS_1_23") (pintype "power_in"))
      (node (ref "IC3") (pin "35") (pinfunction "VSS_2_35") (pintype "power_in"))
      (node (ref "IC3") (pin "47") (pinfunction "VSS_3_47") (pintype "power_in"))
      (node (ref "IC3") (pin "8") (pinfunction "VSSA_8") (pintype "power_in"))
      (node (ref "IC4") (pin "1") (pinfunction "GND_1") (pintype "power_in"))
      (node (ref "IC5") (pin "1") (pinfunction "GND_1") (pintype "power_in"))
      (node (ref "IC8") (pin "1") (pinfunction "GND_1") (pintype "power_in"))
      (node (ref "IO1") (pin "4") (pinfunction "4_4") (pintype "passive"))
      (node (ref "IO3") (pin "4") (pinfunction "4_4") (pintype "passive"))
      (node (ref "J1") (pin "GND") (pinfunction "GND_GND") (pintype "bidirectional"))
      (node (ref "J1") (pin "ID") (pinfunction "ID_ID") (pintype "bidirectional"))
      (node (ref "J1") (pin "SHIELD1") (pinfunction "SHIELD_SHIELD1") (pintype "bidirectional"))
      (node (ref "J1") (pin "SHIELD2") (pinfunction "SHIELD_SHIELD2") (pintype "bidirectional"))
      (node (ref "J1") (pin "SHIELD3") (pinfunction "SHIELD_SHIELD3") (pintype "bidirectional"))
      (node (ref "J3") (pin "1") (pinfunction "1_1") (pintype "passive"))
      (node (ref "J7") (pin "GND") (pinfunction "GND_GND") (pintype "bidirectional"))
      (node (ref "J7") (pin "ID") (pinfunction "ID_ID") (pintype "bidirectional"))
      (node (ref "J7") (pin "SHIELD1") (pinfunction "SHIELD_SHIELD1") (pintype "bidirectional"))
      (node (ref "J7") (pin "SHIELD2") (pinfunction "SHIELD_SHIELD2") (pintype "bidirectional"))
      (node (ref "J7") (pin "SHIELD3") (pinfunction "SHIELD_SHIELD3") (pintype "bidirectional"))
      (node (ref "JP1") (pin "6") (pinfunction "GND_6") (pintype "bidirectional"))
      (node (ref "JTAG") (pin "2") (pinfunction "2_2") (pintype "bidirectional"))
      (node (ref "JTAG") (pin "4") (pinfunction "4_4") (pintype "bidirectional"))
      (node (ref "POWER_") (pin "6") (pinfunction "6_6") (pintype "passive"))
      (node (ref "POWER_") (pin "7") (pinfunction "7_7") (pintype "passive"))
      (node (ref "PROGRAM") (pin "3") (pinfunction "S_3") (pintype "passive"))
      (node (ref "PROGRAM") (pin "4") (pinfunction "S1_4") (pintype "passive"))
      (node (ref "PWR") (pin "C") (pinfunction "C_C") (pintype "passive"))
      (node (ref "Q3") (pin "2") (pinfunction "GND_2") (pintype "power_in"))
      (node (ref "Q4") (pin "2") (pinfunction "GND_2") (pintype "power_in"))
      (node (ref "R12") (pin "1") (pinfunction "1_1") (pintype "passive"))
      (node (ref "R21") (pin "2") (pinfunction "2_2") (pintype "passive"))
      (node (ref "R22") (pin "2") (pinfunction "2_2") (pintype "passive"))
      (node (ref "R34") (pin "2") (pinfunction "2_2") (pintype "passive"))
      (node (ref "R39") (pin "2") (pinfunction "2_2") (pintype "passive"))
      (node (ref "R41") (pin "2") (pinfunction "2_2") (pintype "passive"))
      (node (ref "R6") (pin "2") (pinfunction "2_2") (pintype "passive"))
      (node (ref "R9") (pin "2") (pinfunction "2_2") (pintype "passive"))
      (node (ref "RESET") (pin "3") (pinfunction "S_3") (pintype "passive"))
      (node (ref "RESET") (pin "4") (pinfunction "S1_4") (pintype "passive"))
      (node (ref "STAT") (pin "C") (pinfunction "C_C") (pintype "passive"))
      (node (ref "U1") (pin "C") (pinfunction "C_C") (pintype "passive"))
      (node (ref "U2") (pin "C") (pinfunction "C_C") (pintype "passive"))
    )
    (net (code "30") (name "Net-(ADC-Pad3)") (class "Default")
      (node (ref "ADC") (pin "3") (pinfunction "3_3") (pintype "passive"))
      (node (ref "REFSEL") (pin "3") (pinfunction "3_3") (pintype "passive"))
    )
    (net (code "31") (name "Net-(ADC-Pad4)") (class "Default")
      (node (ref "ADC") (pin "4") (pinfunction "4_4") (pintype "passive"))
      (node (ref "IC2") (pin "173") (pinfunction "173_173") (pintype "bidirectional"))
    )
    (net (code "32") (name "Net-(ADC-Pad5)") (class "Default")
      (node (ref "ADC") (pin "5") (pinfunction "5_5") (pintype "passive"))
      (node (ref "IC2") (pin "174") (pinfunction "174_174") (pintype "bidirectional"))
    )
    (net (code "33") (name "Net-(ADC-Pad6)") (class "Default")
      (node (ref "ADC") (pin "6") (pinfunction "6_6") (pintype "passive"))
      (node (ref "IC2") (pin "176") (pinfunction "176_176") (pintype "bidirectional"))
    )
    (net (code "34") (name "Net-(BANK1-Pad1)") (class "Default")
      (node (ref "BANK1") (pin "1") (pinfunction "1_1") (pintype "passive"))
      (node (ref "IC2") (pin "2") (pinfunction "2_2") (pintype "bidirectional"))
    )
    (net (code "35") (name "Net-(BANK1B-1)") (class "Default")
      (node (ref "BANK1") (pin "10") (pinfunction "1_10") (pintype "passive"))
      (node (ref "IC2") (pin "16") (pinfunction "16_16") (pintype "bidirectional"))
    )
    (net (code "36") (name "Net-(BANK1C-1)") (class "Default")
      (node (ref "BANK1") (pin "11") (pinfunction "1_11") (pintype "passive"))
      (node (ref "IC2") (pin "17") (pinfunction "17_17") (pintype "bidirectional"))
    )
    (net (code "37") (name "Net-(BANK1D-1)") (class "Default")
      (node (ref "BANK1") (pin "12") (pinfunction "1_12") (pintype "passive"))
      (node (ref "IC2") (pin "19") (pinfunction "19_19") (pintype "bidirectional"))
    )
    (net (code "38") (name "Net-(BANK1E-1)") (class "Default")
      (node (ref "BANK1") (pin "13") (pinfunction "1_13") (pintype "passive"))
      (node (ref "IC2") (pin "22") (pinfunction "22_22") (pintype "bidirectional"))
    )
    (net (code "39") (name "Net-(BANK1F-1)") (class "Default")
      (node (ref "BANK1") (pin "14") (pinfunction "1_14") (pintype "passive"))
      (node (ref "IC2") (pin "23") (pinfunction "23_23") (pintype "bidirectional"))
    )
    (net (code "40") (name "Net-(BANK1I-1)") (class "Default")
      (node (ref "BANK1") (pin "2") (pinfunction "1_2") (pintype "passive"))
      (node (ref "IC2") (pin "3") (pinfunction "3_3") (pintype "bidirectional"))
    )
    (net (code "41") (name "Net-(BANK1J-1)") (class "Default")
      (node (ref "BANK1") (pin "3") (pinfunction "1_3") (pintype "passive"))
      (node (ref "IC2") (pin "4") (pinfunction "4_4") (pintype "bidirectional"))
    )
    (net (code "42") (name "Net-(BANK1K-1)") (class "Default")
      (node (ref "BANK1") (pin "4") (pinfunction "1_4") (pintype "passive"))
      (node (ref "IC2") (pin "6") (pinfunction "6_6") (pintype "bidirectional"))
    )
    (net (code "43") (name "Net-(BANK1L-1)") (class "Default")
      (node (ref "BANK1") (pin "5") (pinfunction "1_5") (pintype "passive"))
      (node (ref "IC2") (pin "8") (pinfunction "8_8") (pintype "bidirectional"))
    )
    (net (code "44") (name "Net-(BANK1M-1)") (class "Default")
      (node (ref "BANK1") (pin "6") (pinfunction "1_6") (pintype "passive"))
      (node (ref "IC2") (pin "10") (pinfunction "DONE_10") (pintype "bidirectional"))
      (node (ref "R16") (pin "2") (pinfunction "2_2") (pintype "passive"))
    )
    (net (code "45") (name "Net-(BANK1N-1)") (class "Default")
      (node (ref "BANK1") (pin "7") (pinfunction "1_7") (pintype "passive"))
      (node (ref "IC2") (pin "11") (pinfunction "11_11") (pintype "bidirectional"))
    )
    (net (code "46") (name "Net-(BANK1O-1)") (class "Default")
      (node (ref "BANK1") (pin "8") (pinfunction "1_8") (pintype "passive"))
      (node (ref "IC2") (pin "14") (pinfunction "14_14") (pintype "bidirectional"))
    )
    (net (code "47") (name "Net-(BANK1P-1)") (class "Default")
      (node (ref "BANK1") (pin "9") (pinfunction "1_9") (pintype "passive"))
      (node (ref "IC2") (pin "15") (pinfunction "15_15") (pintype "bidirectional"))
    )
    (net (code "48") (name "Net-(BANK2-Pad1)") (class "Default")
      (node (ref "BANK2") (pin "1") (pinfunction "1_1") (pintype "passive"))
      (node (ref "IC2") (pin "25") (pinfunction "25_25") (pintype "bidirectional"))
    )
    (net (code "49") (name "Net-(BANK2B-1)") (class "Default")
      (node (ref "BANK2") (pin "10") (pinfunction "1_10") (pintype "passive"))
      (node (ref "IC2") (pin "36") (pinfunction "36_36") (pintype "bidirectional"))
    )
    (net (code "50") (name "Net-(BANK2C-1)") (class "Default")
      (node (ref "BANK2") (pin "11") (pinfunction "1_11") (pintype "passive"))
      (node (ref "IC2") (pin "37") (pinfunction "37_37") (pintype "bidirectional"))
    )
    (net (code "51") (name "Net-(BANK2D-1)") (class "Default")
      (node (ref "BANK2") (pin "12") (pinfunction "1_12") (pintype "passive"))
      (node (ref "IC2") (pin "39") (pinfunction "39_39") (pintype "bidirectional"))
    )
    (net (code "52") (name "Net-(BANK2E-1)") (class "Default")
      (node (ref "BANK2") (pin "13") (pinfunction "1_13") (pintype "passive"))
      (node (ref "IC2") (pin "41") (pinfunction "41_41") (pintype "bidirectional"))
    )
    (net (code "53") (name "Net-(BANK2F-1)") (class "Default")
      (node (ref "BANK2") (pin "14") (pinfunction "1_14") (pintype "passive"))
      (node (ref "IC2") (pin "42") (pinfunction "42_42") (pintype "bidirectional"))
    )
    (net (code "54") (name "Net-(BANK2I-1)") (class "Default")
      (node (ref "BANK2") (pin "2") (pinfunction "1_2") (pintype "passive"))
      (node (ref "IC2") (pin "26") (pinfunction "26_26") (pintype "bidirectional"))
    )
    (net (code "55") (name "Net-(BANK2J-1)") (class "Default")
      (node (ref "BANK2") (pin "3") (pinfunction "1_3") (pintype "passive"))
      (node (ref "IC2") (pin "27") (pinfunction "27_27") (pintype "bidirectional"))
    )
    (net (code "56") (name "Net-(BANK2K-1)") (class "Default")
      (node (ref "BANK2") (pin "4") (pinfunction "1_4") (pintype "passive"))
      (node (ref "IC2") (pin "28") (pinfunction "28_28") (pintype "bidirectional"))
    )
    (net (code "57") (name "Net-(BANK2L-1)") (class "Default")
      (node (ref "BANK2") (pin "5") (pinfunction "1_5") (pintype "passive"))
      (node (ref "IC2") (pin "29") (pinfunction "29_29") (pintype "bidirectional"))
    )
    (net (code "58") (name "Net-(BANK2M-1)") (class "Default")
      (node (ref "BANK2") (pin "6") (pinfunction "1_6") (pintype "passive"))
      (node (ref "IC2") (pin "30") (pinfunction "30_30") (pintype "bidirectional"))
    )
    (net (code "59") (name "Net-(BANK2N-1)") (class "Default")
      (node (ref "BANK2") (pin "7") (pinfunction "1_7") (pintype "passive"))
      (node (ref "IC2") (pin "31") (pinfunction "31_31") (pintype "bidirectional"))
    )
    (net (code "60") (name "Net-(BANK2O-1)") (class "Default")
      (node (ref "BANK2") (pin "8") (pinfunction "1_8") (pintype "passive"))
      (node (ref "IC2") (pin "32") (pinfunction "32_32") (pintype "bidirectional"))
    )
    (net (code "61") (name "Net-(BANK2P-1)") (class "Default")
      (node (ref "BANK2") (pin "9") (pinfunction "1_9") (pintype "passive"))
      (node (ref "IC2") (pin "35") (pinfunction "35_35") (pintype "bidirectional"))
    )
    (net (code "62") (name "Net-(C40-Pad1)") (class "Default")
      (node (ref "C40") (pin "1") (pinfunction "1_1") (pintype "passive"))
      (node (ref "JP1") (pin "GND3") (pinfunction "SHIELD_GND3") (pintype "bidirectional"))
    )
    (net (code "63") (name "Net-(IC2-ADC_REF)") (class "Default")
      (node (ref "C10") (pin "2") (pinfunction "2_2") (pintype "passive"))
      (node (ref "IC2") (pin "172") (pinfunction "ADC_REF_172") (pintype "bidirectional"))
      (node (ref "REFSEL") (pin "2") (pinfunction "2_2") (pintype "passive"))
    )
    (net (code "64") (name "Net-(IC2-DDR_VREF)") (class "Default")
      (node (ref "IC2") (pin "5") (pinfunction "DDR_VREF_5") (pintype "bidirectional"))
      (node (ref "R8") (pin "2") (pinfunction "2_2") (pintype "passive"))
      (node (ref "R9") (pin "1") (pinfunction "1_1") (pintype "passive"))
    )
    (net (code "65") (name "Net-(IC2-HSWAPEN)") (class "Default")
      (node (ref "HSWAPEN") (pin "1") (pinfunction "1_1") (pintype "passive"))
      (node (ref "IC2") (pin "88") (pinfunction "HSWAPEN_88") (pintype "bidirectional"))
      (node (ref "R14") (pin "1") (pinfunction "1_1") (pintype "passive"))
    )
    (net (code "66") (name "Net-(IC2-INIT)") (class "Default")
      (node (ref "IC2") (pin "139") (pinfunction "INIT_139") (pintype "bidirectional"))
      (node (ref "R15") (pin "2") (pinfunction "2_2") (pintype "passive"))
    )
    (net (code "67") (name "Net-(IC2-MSEL0)") (class "Default")
      (node (ref "ADC") (pin "1") (pinfunction "1_1") (pintype "passive"))
      (node (ref "IC2") (pin "169") (pinfunction "MSEL0_169") (pintype "bidirectional"))
      (node (ref "R13") (pin "2") (pinfunction "2_2") (pintype "passive"))
    )
    (net (code "68") (name "Net-(IC2-MSEL1)") (class "Default")
      (node (ref "ADC") (pin "2") (pinfunction "2_2") (pintype "passive"))
      (node (ref "IC2") (pin "170") (pinfunction "MSEL1_170") (pintype "bidirectional"))
      (node (ref "R12") (pin "2") (pinfunction "2_2") (pintype "passive"))
    )
    (net (code "69") (name "Net-(IC2-Pad49)") (class "Default")
      (node (ref "IC2") (pin "49") (pinfunction "49_49") (pintype "bidirectional"))
      (node (ref "IO2") (pin "8") (pinfunction "8_8") (pintype "passive"))
    )
    (net (code "70") (name "Net-(IC2-Pad50)") (class "Default")
      (node (ref "IC2") (pin "50") (pinfunction "50_50") (pintype "bidirectional"))
      (node (ref "IO4") (pin "8") (pinfunction "8_8") (pintype "passive"))
    )
    (net (code "71") (name "Net-(IC2-Pad51)") (class "Default")
      (node (ref "IC2") (pin "51") (pinfunction "51_51") (pintype "bidirectional"))
      (node (ref "IO2") (pin "7") (pinfunction "7_7") (pintype "passive"))
    )
    (net (code "72") (name "Net-(IC2-Pad52)") (class "Default")
      (node (ref "IC2") (pin "52") (pinfunction "52_52") (pintype "bidirectional"))
      (node (ref "IO4") (pin "7") (pinfunction "7_7") (pintype "passive"))
    )
    (net (code "73") (name "Net-(IC2-Pad53)") (class "Default")
      (node (ref "IC2") (pin "53") (pinfunction "53_53") (pintype "bidirectional"))
      (node (ref "IO2") (pin "6") (pinfunction "6_6") (pintype "passive"))
    )
    (net (code "74") (name "Net-(IC2-Pad54)") (class "Default")
      (node (ref "IC2") (pin "54") (pinfunction "54_54") (pintype "bidirectional"))
      (node (ref "IO4") (pin "6") (pinfunction "6_6") (pintype "passive"))
    )
    (net (code "75") (name "Net-(IC2-Pad55)") (class "Default")
      (node (ref "IC2") (pin "55") (pinfunction "55_55") (pintype "bidirectional"))
      (node (ref "IO2") (pin "5") (pinfunction "5_5") (pintype "passive"))
    )
    (net (code "76") (name "Net-(IC2-Pad56)") (class "Default")
      (node (ref "IC2") (pin "56") (pinfunction "56_56") (pintype "bidirectional"))
      (node (ref "IO4") (pin "5") (pinfunction "5_5") (pintype "passive"))
    )
    (net (code "77") (name "Net-(IC2-Pad57)") (class "Default")
      (node (ref "IC2") (pin "57") (pinfunction "57_57") (pintype "bidirectional"))
      (node (ref "IO2") (pin "4") (pinfunction "4_4") (pintype "passive"))
    )
    (net (code "78") (name "Net-(IC2-Pad58)") (class "Default")
      (node (ref "IC2") (pin "58") (pinfunction "58_58") (pintype "bidirectional"))
      (node (ref "IO4") (pin "4") (pinfunction "4_4") (pintype "passive"))
    )
    (net (code "79") (name "Net-(IC2-Pad60)") (class "Default")
      (node (ref "IC2") (pin "60") (pinfunction "60_60") (pintype "bidirectional"))
      (node (ref "IO2") (pin "3") (pinfunction "3_3") (pintype "passive"))
    )
    (net (code "80") (name "Net-(IC2-Pad61)") (class "Default")
      (node (ref "IC2") (pin "61") (pinfunction "61_61") (pintype "bidirectional"))
      (node (ref "IO4") (pin "3") (pinfunction "3_3") (pintype "passive"))
    )
    (net (code "81") (name "Net-(IC2-Pad62)") (class "Default")
      (node (ref "IC2") (pin "62") (pinfunction "62_62") (pintype "bidirectional"))
      (node (ref "IO2") (pin "2") (pinfunction "2_2") (pintype "passive"))
    )
    (net (code "82") (name "Net-(IC2-Pad63)") (class "Default")
      (node (ref "IC2") (pin "63") (pinfunction "63_63") (pintype "bidirectional"))
      (node (ref "IO4") (pin "2") (pinfunction "2_2") (pintype "passive"))
    )
    (net (code "83") (name "Net-(IC2-Pad64)") (class "Default")
      (node (ref "IC2") (pin "64") (pinfunction "64_64") (pintype "bidirectional"))
      (node (ref "IO2") (pin "1") (pinfunction "1_1") (pintype "passive"))
    )
    (net (code "84") (name "Net-(IC2-Pad66)") (class "Default")
      (node (ref "IC2") (pin "66") (pinfunction "66_66") (pintype "bidirectional"))
      (node (ref "IO4") (pin "1") (pinfunction "1_1") (pintype "passive"))
    )
    (net (code "85") (name "Net-(IC2-Pad68)") (class "Default")
      (node (ref "IC2") (pin "68") (pinfunction "68_68") (pintype "bidirectional"))
      (node (ref "R25") (pin "1") (pinfunction "1_1") (pintype "passive"))
    )
    (net (code "86") (name "Net-(IC2-Pad69)") (class "Default")
      (node (ref "IC2") (pin "69") (pinfunction "69_69") (pintype "bidirectional"))
      (node (ref "IO1") (pin "10") (pinfunction "10_10") (pintype "passive"))
    )
    (net (code "87") (name "Net-(IC2-Pad70)") (class "Default")
      (node (ref "IC2") (pin "70") (pinfunction "70_70") (pintype "bidirectional"))
      (node (ref "IO3") (pin "10") (pinfunction "10_10") (pintype "passive"))
    )
    (net (code "88") (name "Net-(IC2-Pad71)") (class "Default")
      (node (ref "IC2") (pin "71") (pinfunction "71_71") (pintype "bidirectional"))
      (node (ref "IO1") (pin "9") (pinfunction "9_9") (pintype "passive"))
    )
    (net (code "89") (name "Net-(IC2-Pad72)") (class "Default")
      (node (ref "IC2") (pin "72") (pinfunction "72_72") (pintype "bidirectional"))
      (node (ref "IO3") (pin "9") (pinfunction "9_9") (pintype "passive"))
    )
    (net (code "90") (name "Net-(IC2-Pad73)") (class "Default")
      (node (ref "IC2") (pin "73") (pinfunction "73_73") (pintype "bidirectional"))
      (node (ref "IO1") (pin "8") (pinfunction "8_8") (pintype "passive"))
    )
    (net (code "91") (name "Net-(IC2-Pad74)") (class "Default")
      (node (ref "IC2") (pin "74") (pinfunction "74_74") (pintype "bidirectional"))
      (node (ref "IO3") (pin "8") (pinfunction "8_8") (pintype "passive"))
    )
    (net (code "92") (name "Net-(IC2-Pad75)") (class "Default")
      (node (ref "IC2") (pin "75") (pinfunction "75_75") (pintype "bidirectional"))
      (node (ref "IO1") (pin "7") (pinfunction "7_7") (pintype "passive"))
    )
    (net (code "93") (name "Net-(IC2-Pad76)") (class "Default")
      (node (ref "IC2") (pin "76") (pinfunction "76_76") (pintype "bidirectional"))
      (node (ref "IO3") (pin "7") (pinfunction "7_7") (pintype "passive"))
    )
    (net (code "94") (name "Net-(IC2-Pad77)") (class "Default")
      (node (ref "IC2") (pin "77") (pinfunction "77_77") (pintype "bidirectional"))
      (node (ref "IO1") (pin "6") (pinfunction "6_6") (pintype "passive"))
    )
    (net (code "95") (name "Net-(IC2-Pad78)") (class "Default")
      (node (ref "IC2") (pin "78") (pinfunction "78_78") (pintype "bidirectional"))
      (node (ref "IO3") (pin "6") (pinfunction "6_6") (pintype "passive"))
    )
    (net (code "96") (name "Net-(IC2-Pad79)") (class "Default")
      (node (ref "IC2") (pin "79") (pinfunction "79_79") (pintype "bidirectional"))
      (node (ref "IO1") (pin "5") (pinfunction "5_5") (pintype "passive"))
    )
    (net (code "97") (name "Net-(IC2-Pad81)") (class "Default")
      (node (ref "IC2") (pin "81") (pinfunction "81_81") (pintype "bidirectional"))
      (node (ref "IO3") (pin "5") (pinfunction "5_5") (pintype "passive"))
    )
    (net (code "98") (name "Net-(IC2-Pad82)") (class "Default")
      (node (ref "IC2") (pin "82") (pinfunction "82_82") (pintype "bidirectional"))
      (node (ref "IO1") (pin "3") (pinfunction "3_3") (pintype "passive"))
    )
    (net (code "99") (name "Net-(IC2-Pad83)") (class "Default")
      (node (ref "IC2") (pin "83") (pinfunction "83_83") (pintype "bidirectional"))
      (node (ref "IO3") (pin "3") (pinfunction "3_3") (pintype "passive"))
    )
    (net (code "100") (name "Net-(IC2-Pad84)") (class "Default")
      (node (ref "IC2") (pin "84") (pinfunction "84_84") (pintype "bidirectional"))
      (node (ref "IO1") (pin "2") (pinfunction "2_2") (pintype "passive"))
    )
    (net (code "101") (name "Net-(IC2-Pad86)") (class "Default")
      (node (ref "IC2") (pin "86") (pinfunction "86_86") (pintype "bidirectional"))
      (node (ref "IO3") (pin "2") (pinfunction "2_2") (pintype "passive"))
    )
    (net (code "102") (name "Net-(IC2-Pad89)") (class "Default")
      (node (ref "IC2") (pin "89") (pinfunction "89_89") (pintype "bidirectional"))
      (node (ref "IO1") (pin "1") (pinfunction "1_1") (pintype "passive"))
    )
    (net (code "103") (name "Net-(IC2-Pad90)") (class "Default")
      (node (ref "IC2") (pin "90") (pinfunction "90_90") (pintype "bidirectional"))
      (node (ref "IO3") (pin "1") (pinfunction "1_1") (pintype "passive"))
    )
    (net (code "104") (name "Net-(IC2-Pad115)") (class "Default")
      (node (ref "IC2") (pin "115") (pinfunction "115_115") (pintype "bidirectional"))
      (node (ref "U5") (pin "A") (pinfunction "A_A") (pintype "passive"))
    )
    (net (code "105") (name "Net-(IC2-Pad118)") (class "Default")
      (node (ref "IC2") (pin "118") (pinfunction "118_118") (pintype "bidirectional"))
      (node (ref "U4") (pin "A") (pinfunction "A_A") (pintype "passive"))
    )
    (net (code "106") (name "Net-(IC2-Pad119)") (class "Default")
      (node (ref "IC2") (pin "119") (pinfunction "119_119") (pintype "bidirectional"))
      (node (ref "U3") (pin "A") (pinfunction "A_A") (pintype "passive"))
    )
    (net (code "107") (name "Net-(IC2-Pad138)") (class "Default")
      (node (ref "IC2") (pin "138") (pinfunction "138_138") (pintype "bidirectional"))
      (node (ref "R24") (pin "1") (pinfunction "1_1") (pintype "passive"))
    )
    (net (code "108") (name "Net-(IC2-VCCAUX)") (class "Default")
      (node (ref "C22") (pin "2") (pinfunction "2_2") (pintype "passive"))
      (node (ref "IC2") (pin "45") (pinfunction "VCCAUX_45") (pintype "bidirectional"))
      (node (ref "R19") (pin "2") (pinfunction "2_2") (pintype "passive"))
    )
    (net (code "109") (name "Net-(IC2-VCCAUX2)") (class "Default")
      (node (ref "C23") (pin "2") (pinfunction "2_2") (pintype "passive"))
      (node (ref "IC2") (pin "87") (pinfunction "VCCAUX2_87") (pintype "bidirectional"))
      (node (ref "R20") (pin "2") (pinfunction "2_2") (pintype "passive"))
    )
    (net (code "110") (name "Net-(IC2-VCCAUX4)") (class "Default")
      (node (ref "C21") (pin "2") (pinfunction "2_2") (pintype "passive"))
      (node (ref "IC2") (pin "135") (pinfunction "VCCAUX4_135") (pintype "bidirectional"))
      (node (ref "R18") (pin "2") (pinfunction "2_2") (pintype "passive"))
    )
    (net (code "111") (name "Net-(IC2-VCCAUX5)") (class "Default")
      (node (ref "C20") (pin "2") (pinfunction "2_2") (pintype "passive"))
      (node (ref "IC2") (pin "175") (pinfunction "VCCAUX5_175") (pintype "bidirectional"))
      (node (ref "R17") (pin "2") (pinfunction "2_2") (pintype "passive"))
    )
    (net (code "112") (name "Net-(IC2-{slash}PROGRAM)") (class "Default")
      (node (ref "IC2") (pin "134") (pinfunction "/PROGRAM_134") (pintype "bidirectional"))
      (node (ref "PROGRAM") (pin "1") (pinfunction "P_1") (pintype "passive"))
      (node (ref "PROGRAM") (pin "2") (pinfunction "P1_2") (pintype "passive"))
      (node (ref "R10") (pin "2") (pinfunction "2_2") (pintype "passive"))
    )
    (net (code "113") (name "Net-(IC3B-PA8)") (class "Default")
      (node (ref "IC3") (pin "29") (pinfunction "PA8_29") (pintype "bidirectional"))
      (node (ref "R3") (pin "1") (pinfunction "1_1") (pintype "passive"))
    )
    (net (code "114") (name "Net-(IC3B-PA9)") (class "Default")
      (node (ref "IC3") (pin "30") (pinfunction "PA9_30") (pintype "bidirectional"))
      (node (ref "J4") (pin "1") (pinfunction "1_1") (pintype "passive"))
    )
    (net (code "115") (name "Net-(IC3B-PA10)") (class "Default")
      (node (ref "IC3") (pin "31") (pinfunction "PA10_31") (pintype "bidirectional"))
      (node (ref "J2") (pin "1") (pinfunction "1_1") (pintype "passive"))
    )
    (net (code "116") (name "Net-(IC3B-PA11)") (class "Default")
      (node (ref "IC3") (pin "32") (pinfunction "PA11_32") (pintype "bidirectional"))
      (node (ref "R1") (pin "2") (pinfunction "2_2") (pintype "passive"))
    )
    (net (code "117") (name "Net-(IC3B-PA12)") (class "Default")
      (node (ref "IC3") (pin "33") (pinfunction "PA12_33") (pintype "bidirectional"))
      (node (ref "R2") (pin "2") (pinfunction "2_2") (pintype "passive"))
      (node (ref "R3") (pin "2") (pinfunction "2_2") (pintype "passive"))
    )
    (net (code "118") (name "Net-(IC3B-PA13)") (class "Default")
      (node (ref "IC3") (pin "34") (pinfunction "PA13_34") (pintype "bidirectional"))
      (node (ref "J5") (pin "1") (pinfunction "1_1") (pintype "passive"))
    )
    (net (code "119") (name "Net-(IC3B-PA14)") (class "Default")
      (node (ref "IC3") (pin "37") (pinfunction "PA14_37") (pintype "bidirectional"))
      (node (ref "J6") (pin "1") (pinfunction "1_1") (pintype "passive"))
    )
    (net (code "120") (name "Net-(IC3D-PB11)") (class "Default")
      (node (ref "IC3") (pin "22") (pinfunction "PB11_22") (pintype "bidirectional"))
      (node (ref "R5") (pin "1") (pinfunction "1_1") (pintype "passive"))
    )
    (net (code "121") (name "Net-(IC3G-PD0{slash}OSC<=)") (class "Default")
      (node (ref "C4") (pin "1") (pinfunction "1_1") (pintype "passive"))
      (node (ref "IC3") (pin "5") (pinfunction "PD0/OSC<=_5") (pintype "bidirectional"))
      (node (ref "Q1") (pin "2") (pinfunction "2_2") (pintype "passive"))
    )
    (net (code "122") (name "Net-(IC3G-PD1{slash}OSC=>)") (class "Default")
      (node (ref "C5") (pin "1") (pinfunction "1_1") (pintype "passive"))
      (node (ref "IC3") (pin "6") (pinfunction "PD1/OSC=>_6") (pintype "bidirectional"))
      (node (ref "Q1") (pin "1") (pinfunction "1_1") (pintype "passive"))
    )
    (net (code "123") (name "Net-(IC3I-BOOT0)") (class "Default")
      (node (ref "IC3") (pin "44") (pinfunction "BOOT0_44") (pintype "input"))
      (node (ref "R6") (pin "1") (pinfunction "1_1") (pintype "passive"))
    )
    (net (code "124") (name "Net-(IC3I-NRST)") (class "Default")
      (node (ref "IC3") (pin "7") (pinfunction "NRST_7") (pintype "input"))
      (node (ref "R4") (pin "1") (pinfunction "1_1") (pintype "passive"))
    )
    (net (code "125") (name "Net-(IC8-BST)") (class "Default")
      (node (ref "C29") (pin "1") (pinfunction "1_1") (pintype "passive"))
      (node (ref "IC8") (pin "6") (pinfunction "BST_6") (pintype "bidirectional"))
    )
    (net (code "126") (name "Net-(IC8-FB)") (class "Default")
      (node (ref "IC8") (pin "4") (pinfunction "FB_4") (pintype "bidirectional"))
      (node (ref "R7") (pin "1") (pinfunction "1_1") (pintype "passive"))
    )
    (net (code "127") (name "Net-(IC8-LX)") (class "Default")
      (node (ref "C29") (pin "2") (pinfunction "2_2") (pintype "passive"))
      (node (ref "IC8") (pin "2") (pinfunction "LX_2") (pintype "output"))
      (node (ref "L2") (pin "2") (pinfunction "2_2") (pintype "passive"))
    )
    (net (code "128") (name "Net-(J1-PadD+)") (class "Default")
      (node (ref "J1") (pin "D+") (pinfunction "D+_D+") (pintype "bidirectional"))
      (node (ref "R2") (pin "1") (pinfunction "1_1") (pintype "passive"))
    )
    (net (code "129") (name "Net-(J1-PadD-)") (class "Default")
      (node (ref "J1") (pin "D-") (pinfunction "D-_D-") (pintype "bidirectional"))
      (node (ref "R1") (pin "1") (pinfunction "1_1") (pintype "passive"))
    )
    (net (code "130") (name "Net-(J7-PadD+)") (class "Default")
      (node (ref "J7") (pin "D+") (pinfunction "D+_D+") (pintype "bidirectional"))
      (node (ref "R37") (pin "1") (pinfunction "1_1") (pintype "passive"))
    )
    (net (code "131") (name "Net-(J7-PadD-)") (class "Default")
      (node (ref "J7") (pin "D-") (pinfunction "D-_D-") (pintype "bidirectional"))
      (node (ref "R36") (pin "1") (pinfunction "1_1") (pintype "passive"))
    )
    (net (code "132") (name "Net-(JP1-CMD)") (class "Default")
      (node (ref "JP1") (pin "3") (pinfunction "CMD_3") (pintype "bidirectional"))
      (node (ref "R29") (pin "2") (pinfunction "2_2") (pintype "passive"))
    )
    (net (code "133") (name "Net-(JP1-D0)") (class "Default")
      (node (ref "JP1") (pin "8") (pinfunction "D0_8") (pintype "bidirectional"))
      (node (ref "R32") (pin "2") (pinfunction "2_2") (pintype "passive"))
    )
    (net (code "134") (name "Net-(JP1-D1)") (class "Default")
      (node (ref "JP1") (pin "7") (pinfunction "D1_7") (pintype "bidirectional"))
      (node (ref "R31") (pin "2") (pinfunction "2_2") (pintype "passive"))
    )
    (net (code "135") (name "Net-(JP1-D2)") (class "Default")
      (node (ref "JP1") (pin "1") (pinfunction "D2_1") (pintype "bidirectional"))
      (node (ref "R27") (pin "2") (pinfunction "2_2") (pintype "passive"))
    )
    (net (code "136") (name "Net-(JP1-D3)") (class "Default")
      (node (ref "JP1") (pin "2") (pinfunction "D3_2") (pintype "bidirectional"))
      (node (ref "R28") (pin "2") (pinfunction "2_2") (pintype "passive"))
    )
    (net (code "137") (name "Net-(JP1-SCK)") (class "Default")
      (node (ref "JP1") (pin "5") (pinfunction "SCK_5") (pintype "bidirectional"))
      (node (ref "R30") (pin "2") (pinfunction "2_2") (pintype "passive"))
    )
    (net (code "138") (name "Net-(JP1-VCC)") (class "Default")
      (node (ref "C39") (pin "2") (pinfunction "2_2") (pintype "passive"))
      (node (ref "JP1") (pin "4") (pinfunction "VCC_4") (pintype "bidirectional"))
      (node (ref "R26") (pin "2") (pinfunction "2_2") (pintype "passive"))
    )
    (net (code "139") (name "Net-(PWR-PadA)") (class "Default")
      (node (ref "PWR") (pin "A") (pinfunction "A_A") (pintype "passive"))
      (node (ref "R23") (pin "2") (pinfunction "2_2") (pintype "passive"))
    )
    (net (code "140") (name "Net-(Q3-OUT)") (class "Default")
      (node (ref "IC2") (pin "161") (pinfunction "161_161") (pintype "bidirectional"))
      (node (ref "Q3") (pin "3") (pinfunction "OUT_3") (pintype "output"))
      (node (ref "Q4") (pin "3") (pinfunction "FO_3") (pintype "output"))
    )
    (net (code "141") (name "Net-(R5-Pad2)") (class "Default")
      (node (ref "R5") (pin "2") (pinfunction "2_2") (pintype "passive"))
      (node (ref "STAT") (pin "A") (pinfunction "A_A") (pintype "passive"))
    )
    (net (code "142") (name "Net-(R21-Pad1)") (class "Default")
      (node (ref "R21") (pin "1") (pinfunction "1_1") (pintype "passive"))
      (node (ref "U3") (pin "C") (pinfunction "C_C") (pintype "passive"))
    )
    (net (code "143") (name "Net-(R22-Pad1)") (class "Default")
      (node (ref "R22") (pin "1") (pinfunction "1_1") (pintype "passive"))
      (node (ref "U4") (pin "C") (pinfunction "C_C") (pintype "passive"))
    )
    (net (code "144") (name "Net-(R24-Pad2)") (class "Default")
      (node (ref "R24") (pin "2") (pinfunction "2_2") (pintype "passive"))
      (node (ref "U2") (pin "A") (pinfunction "A_A") (pintype "passive"))
    )
    (net (code "145") (name "Net-(R25-Pad2)") (class "Default")
      (node (ref "R25") (pin "2") (pinfunction "2_2") (pintype "passive"))
      (node (ref "U1") (pin "A") (pinfunction "A_A") (pintype "passive"))
    )
    (net (code "146") (name "Net-(R39-Pad1)") (class "Default")
      (node (ref "R39") (pin "1") (pinfunction "1_1") (pintype "passive"))
      (node (ref "R40") (pin "2") (pinfunction "2_2") (pintype "passive"))
      (node (ref "R7") (pin "2") (pinfunction "2_2") (pintype "passive"))
    )
    (net (code "147") (name "Net-(R41-Pad1)") (class "Default")
      (node (ref "R41") (pin "1") (pinfunction "1_1") (pintype "passive"))
      (node (ref "U5") (pin "C") (pinfunction "C_C") (pintype "passive"))
    )
    (net (code "148") (name "VCCINT") (class "Default")
      (node (ref "C12") (pin "2") (pinfunction "2_2") (pintype "passive"))
      (node (ref "C13") (pin "2") (pinfunction "2_2") (pintype "passive"))
      (node (ref "C14") (pin "2") (pinfunction "2_2") (pintype "passive"))
      (node (ref "C16") (pin "2") (pinfunction "2_2") (pintype "passive"))
      (node (ref "C17") (pin "2") (pinfunction "2_2") (pintype "passive"))
      (node (ref "C33") (pin "2") (pinfunction "2_2") (pintype "passive"))
      (node (ref "C34") (pin "2") (pinfunction "2_2") (pintype "passive"))
      (node (ref "C35") (pin "2") (pinfunction "2_2") (pintype "passive"))
      (node (ref "C36") (pin "2") (pinfunction "2_2") (pintype "passive"))
      (node (ref "IC2") (pin "1") (pinfunction "VCORE_1") (pintype "bidirectional"))
      (node (ref "IC2") (pin "113") (pinfunction "VCORE_113") (pintype "bidirectional"))
      (node (ref "IC2") (pin "128") (pinfunction "VCORE_128") (pintype "bidirectional"))
      (node (ref "IC2") (pin "137") (pinfunction "VCORE_137") (pintype "bidirectional"))
      (node (ref "IC2") (pin "164") (pinfunction "VCORE_164") (pintype "bidirectional"))
      (node (ref "IC2") (pin "20") (pinfunction "VCORE_20") (pintype "bidirectional"))
      (node (ref "IC2") (pin "48") (pinfunction "VCORE_48") (pintype "bidirectional"))
      (node (ref "IC2") (pin "65") (pinfunction "VCORE_65") (pintype "bidirectional"))
      (node (ref "IC2") (pin "85") (pinfunction "VCORE_85") (pintype "bidirectional"))
      (node (ref "IC2") (pin "92") (pinfunction "VCORE_92") (pintype "bidirectional"))
      (node (ref "L2") (pin "1") (pinfunction "1_1") (pintype "passive"))
      (node (ref "R40") (pin "1") (pinfunction "1_1") (pintype "passive"))
    )
    (net (code "149") (name "VCC{slash}2") (class "Default")
      (node (ref "C24") (pin "2") (pinfunction "2_2") (pintype "passive"))
      (node (ref "C25") (pin "2") (pinfunction "2_2") (pintype "passive"))
      (node (ref "C26") (pin "2") (pinfunction "2_2") (pintype "passive"))
      (node (ref "C27") (pin "2") (pinfunction "2_2") (pintype "passive"))
      (node (ref "C6") (pin "1") (pinfunction "1_1") (pintype "passive"))
      (node (ref "IC2") (pin "105") (pinfunction "VCCIO5_105") (pintype "bidirectional"))
      (node (ref "IC2") (pin "108") (pinfunction "VCCIO5_108") (pintype "bidirectional"))
      (node (ref "IC2") (pin "117") (pinfunction "VCCIO6_117") (pintype "bidirectional"))
      (node (ref "IC2") (pin "12") (pinfunction "VCCIO1_12") (pintype "bidirectional"))
      (node (ref "IC2") (pin "120") (pinfunction "VCCIO6_120") (pintype "bidirectional"))
      (node (ref "IC2") (pin "125") (pinfunction "VCCIO6_125") (pintype "bidirectional"))
      (node (ref "IC2") (pin "18") (pinfunction "VCCIO1_18") (pintype "bidirectional"))
      (node (ref "IC2") (pin "24") (pinfunction "VCCIO2_24") (pintype "bidirectional"))
      (node (ref "IC2") (pin "34") (pinfunction "VCCIO2_34") (pintype "bidirectional"))
      (node (ref "IC2") (pin "40") (pinfunction "VCCIO2_40") (pintype "bidirectional"))
      (node (ref "IC2") (pin "7") (pinfunction "VCCIO1_7") (pintype "bidirectional"))
      (node (ref "IC2") (pin "96") (pinfunction "VCCIO5_96") (pintype "bidirectional"))
      (node (ref "IC5") (pin "2") (pinfunction "VOUT_2") (pintype "output"))
      (node (ref "R16") (pin "1") (pinfunction "1_1") (pintype "passive"))
      (node (ref "R8") (pin "1") (pinfunction "1_1") (pintype "passive"))
    )
    (net (code "150") (name "unconnected-(IC2-Pad97)") (class "Default")
      (node (ref "IC2") (pin "97") (pinfunction "97_97") (pintype "bidirectional"))
    )
    (net (code "151") (name "unconnected-(IC2-Pad98)") (class "Default")
      (node (ref "IC2") (pin "98") (pinfunction "98_98") (pintype "bidirectional"))
    )
    (net (code "152") (name "unconnected-(IC2-Pad99)") (class "Default")
      (node (ref "IC2") (pin "99") (pinfunction "99_99") (pintype "bidirectional"))
    )
    (net (code "153") (name "unconnected-(IC2-Pad100)") (class "Default")
      (node (ref "IC2") (pin "100") (pinfunction "100_100") (pintype "bidirectional"))
    )
    (net (code "154") (name "unconnected-(IC2-Pad101)") (class "Default")
      (node (ref "IC2") (pin "101") (pinfunction "101_101") (pintype "bidirectional"))
    )
    (net (code "155") (name "unconnected-(IC2-Pad102)") (class "Default")
      (node (ref "IC2") (pin "102") (pinfunction "102_102") (pintype "bidirectional"))
    )
    (net (code "156") (name "unconnected-(IC2-Pad103)") (class "Default")
      (node (ref "IC2") (pin "103") (pinfunction "103_103") (pintype "bidirectional"))
    )
    (net (code "157") (name "unconnected-(IC2-Pad104)") (class "Default")
      (node (ref "IC2") (pin "104") (pinfunction "104_104") (pintype "bidirectional"))
    )
    (net (code "158") (name "unconnected-(IC2-Pad106)") (class "Default")
      (node (ref "IC2") (pin "106") (pinfunction "106_106") (pintype "bidirectional"))
    )
    (net (code "159") (name "unconnected-(IC2-Pad107)") (class "Default")
      (node (ref "IC2") (pin "107") (pinfunction "107_107") (pintype "bidirectional"))
    )
    (net (code "160") (name "unconnected-(IC2-Pad109)") (class "Default")
      (node (ref "IC2") (pin "109") (pinfunction "109_109") (pintype "bidirectional"))
    )
    (net (code "161") (name "unconnected-(IC2-Pad110)") (class "Default")
      (node (ref "IC2") (pin "110") (pinfunction "110_110") (pintype "bidirectional"))
    )
    (net (code "162") (name "unconnected-(IC2-Pad111)") (class "Default")
      (node (ref "IC2") (pin "111") (pinfunction "111_111") (pintype "bidirectional"))
    )
    (net (code "163") (name "unconnected-(IC2-Pad112)") (class "Default")
      (node (ref "IC2") (pin "112") (pinfunction "112_112") (pintype "bidirectional"))
    )
    (net (code "164") (name "unconnected-(IC2-Pad114)") (class "Default")
      (node (ref "IC2") (pin "114") (pinfunction "114_114") (pintype "bidirectional"))
    )
    (net (code "165") (name "unconnected-(IC2-Pad121)") (class "Default")
      (node (ref "IC2") (pin "121") (pinfunction "121_121") (pintype "bidirectional"))
    )
    (net (code "166") (name "unconnected-(IC2-Pad122)") (class "Default")
      (node (ref "IC2") (pin "122") (pinfunction "122_122") (pintype "bidirectional"))
    )
    (net (code "167") (name "unconnected-(IC2-Pad123)") (class "Default")
      (node (ref "IC2") (pin "123") (pinfunction "123_123") (pintype "bidirectional"))
    )
    (net (code "168") (name "unconnected-(IC2-Pad124)") (class "Default")
      (node (ref "IC2") (pin "124") (pinfunction "124_124") (pintype "bidirectional"))
    )
    (net (code "169") (name "unconnected-(IC2-Pad126)") (class "Default")
      (node (ref "IC2") (pin "126") (pinfunction "126_126") (pintype "bidirectional"))
    )
    (net (code "170") (name "unconnected-(IC2-Pad127)") (class "Default")
      (node (ref "IC2") (pin "127") (pinfunction "127_127") (pintype "bidirectional"))
    )
    (net (code "171") (name "unconnected-(IC2-Pad129)") (class "Default")
      (node (ref "IC2") (pin "129") (pinfunction "129_129") (pintype "bidirectional"))
    )
    (net (code "172") (name "unconnected-(IC2-Pad130)") (class "Default")
      (node (ref "IC2") (pin "130") (pinfunction "130_130") (pintype "bidirectional"))
    )
    (net (code "173") (name "unconnected-(IC2-Pad131)") (class "Default")
      (node (ref "IC2") (pin "131") (pinfunction "131_131") (pintype "bidirectional"))
    )
    (net (code "174") (name "unconnected-(IC2-Pad132)") (class "Default")
      (node (ref "IC2") (pin "132") (pinfunction "132_132") (pintype "bidirectional"))
    )
    (net (code "175") (name "unconnected-(IC2-Pad133)") (class "Default")
      (node (ref "IC2") (pin "133") (pinfunction "133_133") (pintype "bidirectional"))
    )
    (net (code "176") (name "unconnected-(IC2-Pad141)") (class "Default")
      (node (ref "IC2") (pin "141") (pinfunction "141_141") (pintype "bidirectional"))
    )
    (net (code "177") (name "unconnected-(IC2-Pad143)") (class "Default")
      (node (ref "IC2") (pin "143") (pinfunction "143_143") (pintype "bidirectional"))
    )
    (net (code "178") (name "unconnected-(IC2-Pad146)") (class "Default")
      (node (ref "IC2") (pin "146") (pinfunction "146_146") (pintype "bidirectional"))
    )
    (net (code "179") (name "unconnected-(IC2-Pad147)") (class "Default")
      (node (ref "IC2") (pin "147") (pinfunction "147_147") (pintype "bidirectional"))
    )
    (net (code "180") (name "unconnected-(IC2-Pad149)") (class "Default")
      (node (ref "IC2") (pin "149") (pinfunction "149_149") (pintype "bidirectional"))
    )
    (net (code "181") (name "unconnected-(IC2-Pad158)") (class "Default")
      (node (ref "IC2") (pin "158") (pinfunction "158_158") (pintype "bidirectional"))
    )
    (net (code "182") (name "unconnected-(IC2-Pad159)") (class "Default")
      (node (ref "IC2") (pin "159") (pinfunction "159_159") (pintype "bidirectional"))
    )
    (net (code "183") (name "unconnected-(IC3B-PA15-Pad38)") (class "Default")
      (node (ref "IC3") (pin "38") (pinfunction "PA15_38") (pintype "bidirectional"))
    )
    (net (code "184") (name "unconnected-(IC3D-PB8-Pad45)") (class "Default")
      (node (ref "IC3") (pin "45") (pinfunction "PB8_45") (pintype "bidirectional"))
    )
    (net (code "185") (name "unconnected-(IC3D-PB9-Pad46)") (class "Default")
      (node (ref "IC3") (pin "46") (pinfunction "PB9_46") (pintype "bidirectional"))
    )
    (net (code "186") (name "unconnected-(IC3D-PB10-Pad21)") (class "Default")
      (node (ref "IC3") (pin "21") (pinfunction "PB10_21") (pintype "bidirectional"))
    )
    (net (code "187") (name "unconnected-(IC3E-PB7-Pad43)") (class "Default")
      (node (ref "IC3") (pin "43") (pinfunction "PB7_43") (pintype "bidirectional"))
    )
    (net (code "188") (name "unconnected-(IC3F-PC13-Pad2)") (class "Default")
      (node (ref "IC3") (pin "2") (pinfunction "PC13_2") (pintype "bidirectional"))
    )
    (net (code "189") (name "unconnected-(IC3F-PC14-Pad3)") (class "Default")
      (node (ref "IC3") (pin "3") (pinfunction "PC14_3") (pintype "bidirectional"))
    )
    (net (code "190") (name "unconnected-(IC3F-PC15-Pad4)") (class "Default")
      (node (ref "IC3") (pin "4") (pinfunction "PC15_4") (pintype "bidirectional"))
    )
    (net (code "191") (name "unconnected-(JP1-PadCD1)") (class "Default")
      (node (ref "JP1") (pin "CD1") (pinfunction "CD1_CD1") (pintype "bidirectional"))
    )
    (net (code "192") (name "unconnected-(JP1-SHIELD-PadGND1)") (class "Default")
      (node (ref "JP1") (pin "GND1") (pinfunction "SHIELD_GND1") (pintype "bidirectional"))
    )
    (net (code "193") (name "unconnected-(POWER_-Pad1)") (class "Default")
      (node (ref "POWER_") (pin "1") (pinfunction "1_1") (pintype "passive"))
    )
    (net (code "194") (name "unconnected-(POWER_-Pad8)") (class "Default")
      (node (ref "POWER_") (pin "8") (pinfunction "8_8") (pintype "passive"))
    )
  )
)
